# ProPrj__G__2025-07-30.net
KiCad netlist of a schematic drawn in EasyEDA Pro
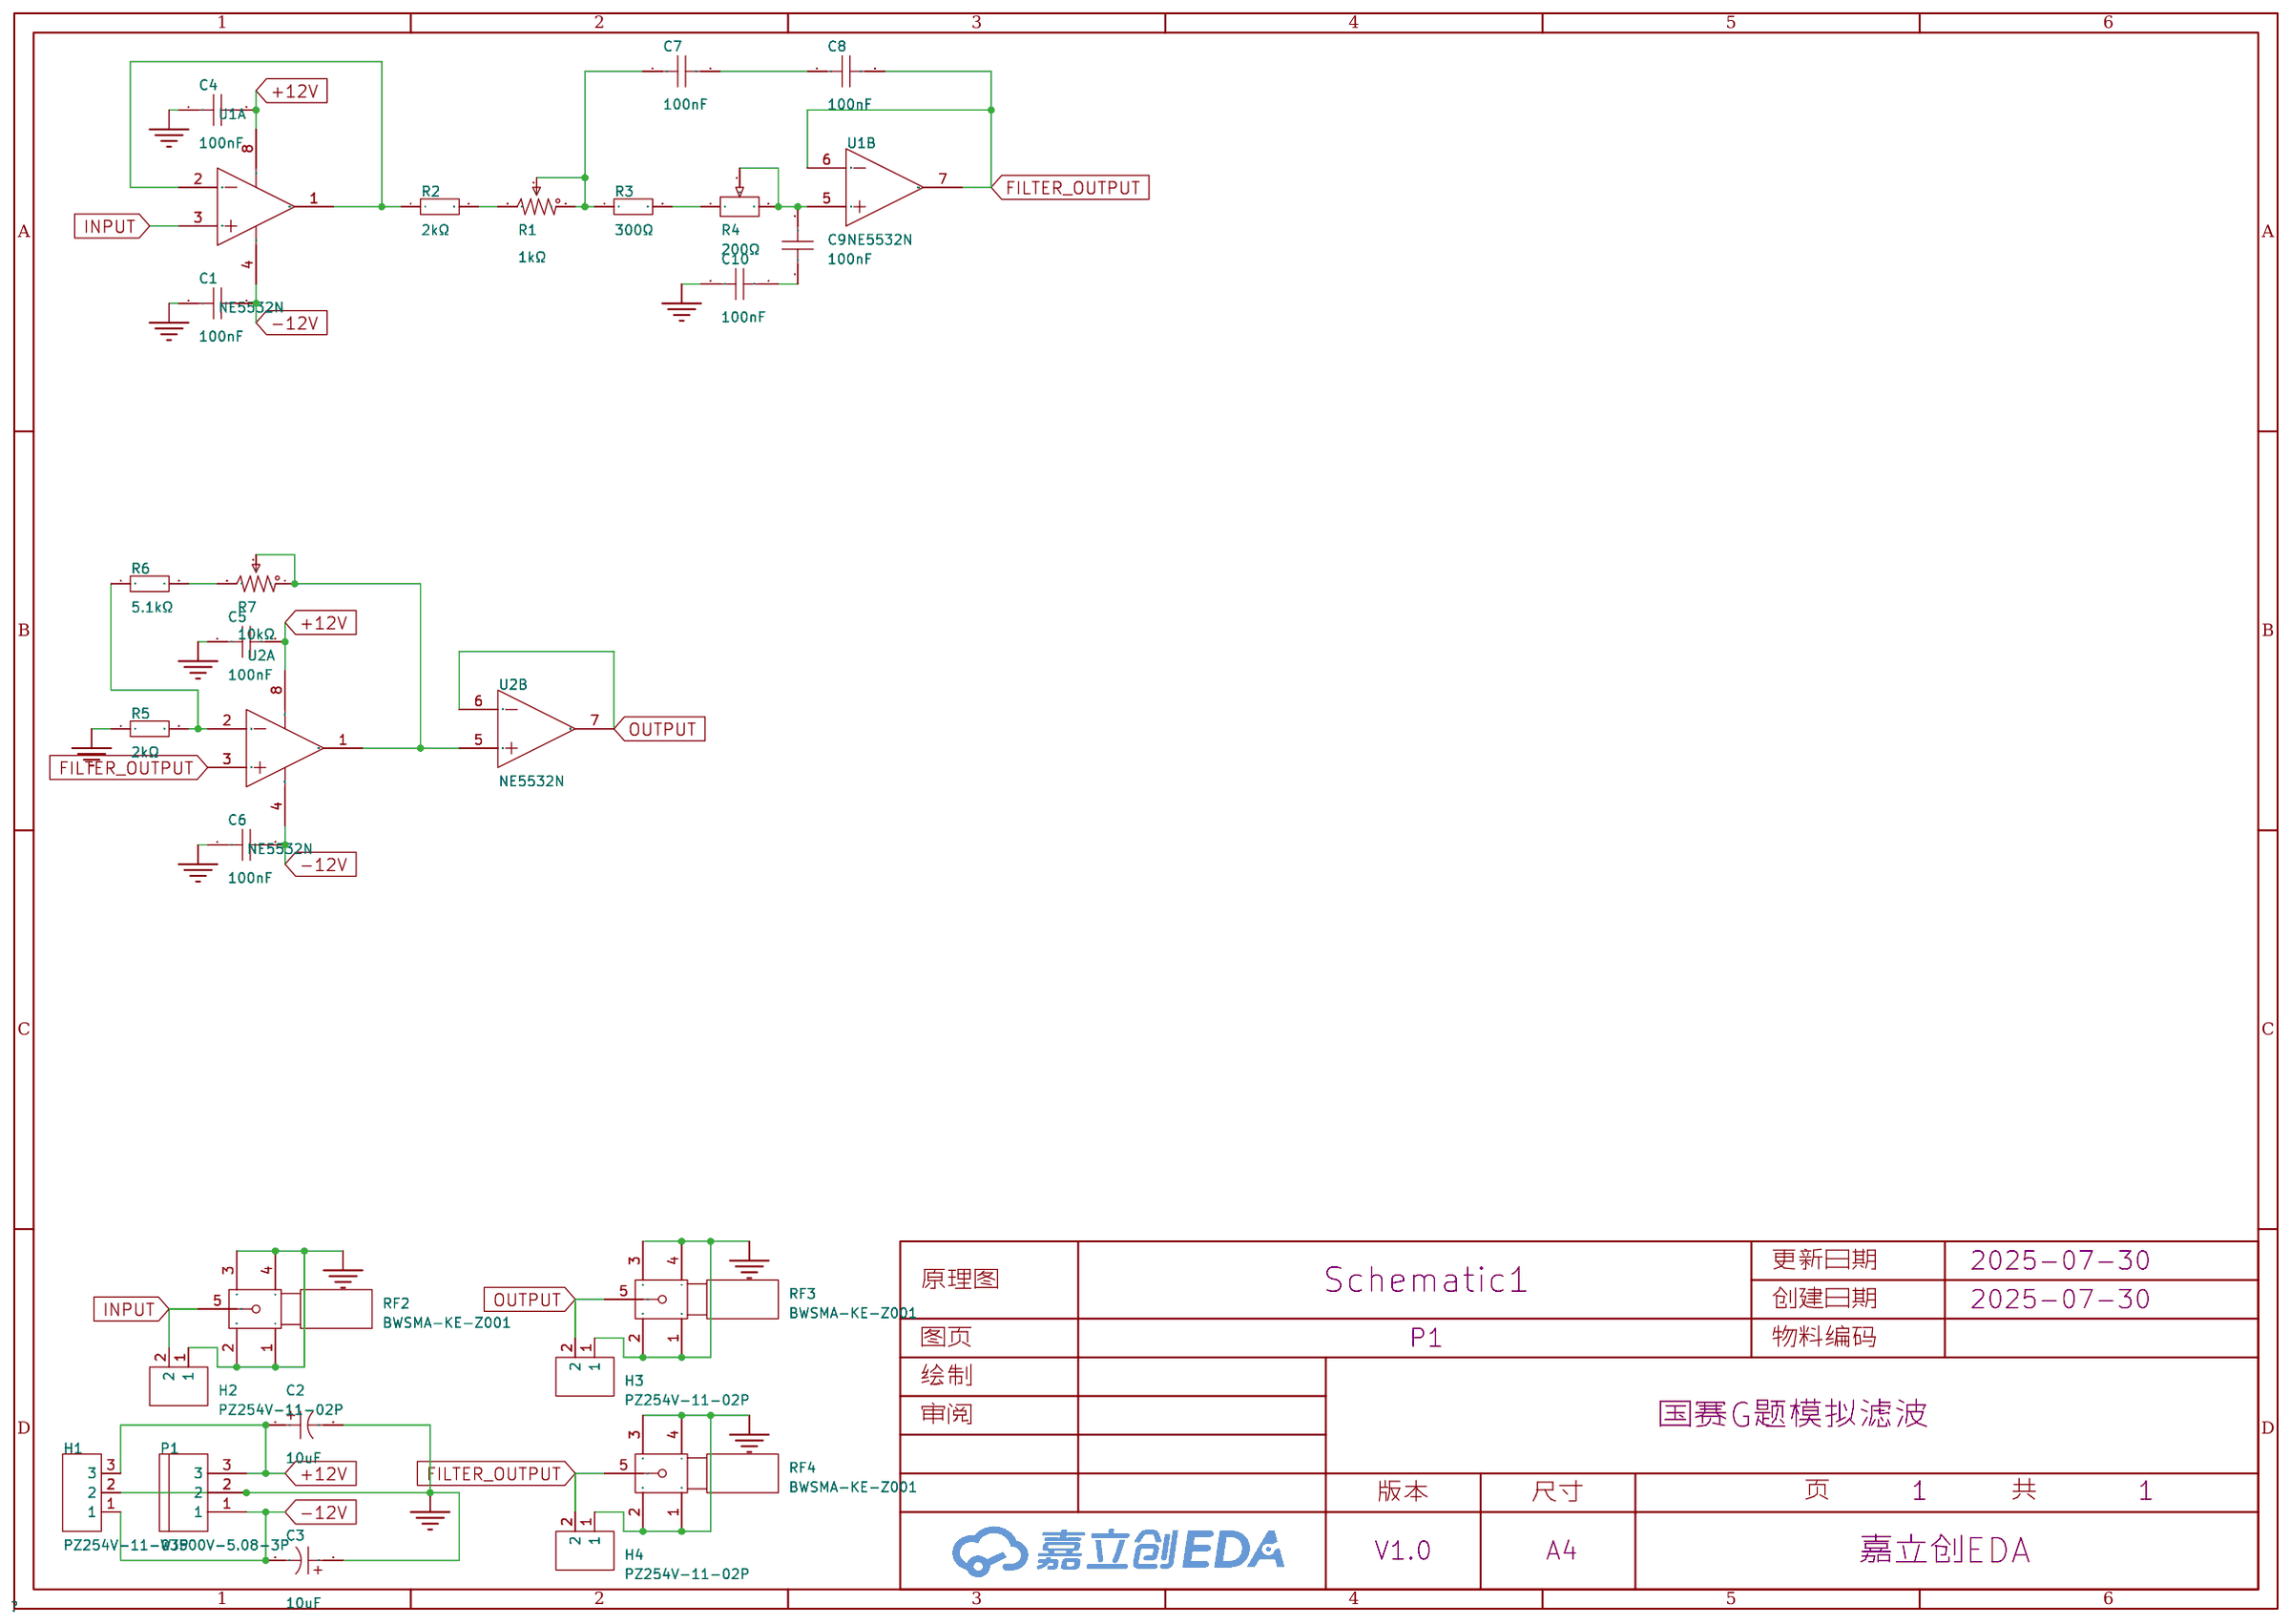
[diagram p0: schematic sheet]

(export (version "E")
  (design (tool "Eeschema 10.0.6"))
  (components
    (comp (ref "C1")
      (value "100nF")
      (footprint "easyedapro:CAP-TH_L5.8-W2.4-P2.54-D0.6")
      (description "容值:100nF;精度:-20%~+80%;额定电压:50V;温度系数:Y5V;")
      (fields
        (field (name "Manufacturer Part") "CC1H104ZA1ED3F5P1100")
        (field (name "Manufacturer") "Dersonic(德尔创)")
      )
      (libsource (lib "easyedapro") (part "CC1H104ZA1ED3F5P1100"))
    )
    (comp (ref "C2")
      (value "10uF")
      (footprint "easyedapro:CAP-TH_BD5.0-P2.00-D0.5-FD-A")
      (description "容值:10uF;精度:±20%;额定电压:25V;纹波电流:100mA@100kHz;等效串联电阻(ESR):3.3Ω@100kHz;")
      (fields (field (name "Manufacturer Part") "ERG450V10M10x16") (field (name "Manufacturer") "捷而瑞"))
      (libsource (lib "easyedapro") (part "ERG25V10M5X11"))
    )
    (comp (ref "C3")
      (value "10uF")
      (footprint "easyedapro:CAP-TH_BD5.0-P2.00-D0.5-FD-A")
      (description "容值:10uF;精度:±20%;额定电压:25V;纹波电流:100mA@100kHz;等效串联电阻(ESR):3.3Ω@100kHz;")
      (fields (field (name "Manufacturer Part") "ERG450V10M10x16") (field (name "Manufacturer") "捷而瑞"))
      (libsource (lib "easyedapro") (part "ERG25V10M5X11"))
    )
    (comp (ref "C4")
      (value "100nF")
      (footprint "easyedapro:CAP-TH_L5.8-W2.4-P2.54-D0.6")
      (description "容值:100nF;精度:-20%~+80%;额定电压:50V;温度系数:Y5V;")
      (fields
        (field (name "Manufacturer Part") "CC1H104ZA1ED3F5P1100")
        (field (name "Manufacturer") "Dersonic(德尔创)")
      )
      (libsource (lib "easyedapro") (part "CC1H104ZA1ED3F5P1100"))
    )
    (comp (ref "C5")
      (value "100nF")
      (footprint "easyedapro:CAP-TH_L5.8-W2.4-P2.54-D0.6")
      (description "容值:100nF;精度:-20%~+80%;额定电压:50V;温度系数:Y5V;")
      (fields
        (field (name "Manufacturer Part") "CC1H104ZA1ED3F5P1100")
        (field (name "Manufacturer") "Dersonic(德尔创)")
      )
      (libsource (lib "easyedapro") (part "CC1H104ZA1ED3F5P1100"))
    )
    (comp (ref "C6")
      (value "100nF")
      (footprint "easyedapro:CAP-TH_L5.8-W2.4-P2.54-D0.6")
      (description "容值:100nF;精度:-20%~+80%;额定电压:50V;温度系数:Y5V;")
      (fields
        (field (name "Manufacturer Part") "CC1H104ZA1ED3F5P1100")
        (field (name "Manufacturer") "Dersonic(德尔创)")
      )
      (libsource (lib "easyedapro") (part "CC1H104ZA1ED3F5P1100"))
    )
    (comp (ref "C7")
      (value "100nF")
      (footprint "easyedapro:CAP-TH_L5.8-W2.4-P2.54-D0.6")
      (description "容值:100nF;精度:-20%~+80%;额定电压:50V;温度系数:Y5V;")
      (fields
        (field (name "Manufacturer Part") "CC1H104ZA1ED3F5P1100")
        (field (name "Manufacturer") "Dersonic(德尔创)")
      )
      (libsource (lib "easyedapro") (part "CC1H104ZA1ED3F5P1100"))
    )
    (comp (ref "C8")
      (value "100nF")
      (footprint "easyedapro:CAP-TH_L5.8-W2.4-P2.54-D0.6")
      (description "容值:100nF;精度:-20%~+80%;额定电压:50V;温度系数:Y5V;")
      (fields
        (field (name "Manufacturer Part") "CC1H104ZA1ED3F5P1100")
        (field (name "Manufacturer") "Dersonic(德尔创)")
      )
      (libsource (lib "easyedapro") (part "CC1H104ZA1ED3F5P1100"))
    )
    (comp (ref "C9")
      (value "100nF")
      (footprint "easyedapro:CAP-TH_L5.8-W2.4-P2.54-D0.6")
      (description "容值:100nF;精度:-20%~+80%;额定电压:50V;温度系数:Y5V;")
      (fields
        (field (name "Manufacturer Part") "CC1H104ZA1ED3F5P1100")
        (field (name "Manufacturer") "Dersonic(德尔创)")
      )
      (libsource (lib "easyedapro") (part "CC1H104ZA1ED3F5P1100"))
    )
    (comp (ref "C10")
      (value "100nF")
      (footprint "easyedapro:CAP-TH_L5.8-W2.4-P2.54-D0.6")
      (description "容值:100nF;精度:-20%~+80%;额定电压:50V;温度系数:Y5V;")
      (fields
        (field (name "Manufacturer Part") "CC1H104ZA1ED3F5P1100")
        (field (name "Manufacturer") "Dersonic(德尔创)")
      )
      (libsource (lib "easyedapro") (part "CC1H104ZA1ED3F5P1100"))
    )
    (comp (ref "H1")
      (value "PZ254V-11-03P")
      (footprint "easyedapro:HDR-TH_3P-P2.54-V-M")
      (fields (field (name "Manufacturer") "XFCN(兴飞)"))
      (libsource (lib "easyedapro") (part "PZ254V-11-03P_C2937625"))
    )
    (comp (ref "H2")
      (value "PZ254V-11-02P")
      (footprint "easyedapro:HDR-TH_2P-P2.54-V-M")
      (fields (field (name "Manufacturer") "XFCN(兴飞)"))
      (libsource (lib "easyedapro") (part "PZ254V-11-02P"))
    )
    (comp (ref "H3")
      (value "PZ254V-11-02P")
      (footprint "easyedapro:HDR-TH_2P-P2.54-V-M")
      (fields (field (name "Manufacturer") "XFCN(兴飞)"))
      (libsource (lib "easyedapro") (part "PZ254V-11-02P"))
    )
    (comp (ref "H4")
      (value "PZ254V-11-02P")
      (footprint "easyedapro:HDR-TH_2P-P2.54-V-M")
      (fields (field (name "Manufacturer") "XFCN(兴飞)"))
      (libsource (lib "easyedapro") (part "PZ254V-11-02P"))
    )
    (comp (ref "P1")
      (value "WJ500V-5.08-3P")
      (footprint "easyedapro:CONN-TH_3P-P5.00_WJ500V-5.08-3P")
      (fields (field (name "Manufacturer") "KANGNEX(康奈克斯电气)"))
      (libsource (lib "easyedapro") (part "WJ500V-5.08-3P-14-00A"))
    )
    (comp (ref "R1")
      (value "1kΩ")
      (footprint "easyedapro:RES-ADJ-TH_3P-L10.0-W10.0-P2.50-BL-BS")
      (description "阻值:1kΩ;精度:±10%;")
      (fields (field (name "Manufacturer Part") "3296W-1-102") (field (name "Manufacturer") "BOCHEN(博晨)"))
      (libsource (lib "easyedapro") (part "3296W-1-102"))
    )
    (comp (ref "R2")
      (value "2kΩ")
      (footprint "easyedapro:Res_1/8W")
      (libsource (lib "easyedapro") (part "电阻"))
    )
    (comp (ref "R3")
      (value "300Ω")
      (footprint "easyedapro:Res_1/8W")
      (libsource (lib "easyedapro") (part "电阻"))
    )
    (comp (ref "R4")
      (value "200Ω")
      (footprint "easyedapro:RES-ADJ-TH_3P-L9.5-W4.9-P2.50-L_3296W")
      (description "阻值:200Ω;精度:±10%;")
      (fields (field (name "Manufacturer Part") "3296W-1-201") (field (name "Manufacturer") "BOCHEN(博晨)"))
      (libsource (lib "easyedapro") (part "3296W-1-201"))
    )
    (comp (ref "R5")
      (value "2kΩ")
      (footprint "easyedapro:Res_1/8W")
      (libsource (lib "easyedapro") (part "电阻"))
    )
    (comp (ref "R6")
      (value "5.1kΩ")
      (footprint "easyedapro:Res_1/8W")
      (libsource (lib "easyedapro") (part "电阻"))
    )
    (comp (ref "R7")
      (value "10kΩ")
      (footprint "easyedapro:RES-ADJ-TH_3P-L10.0-W10.0-P2.50-L")
      (description "阻值:10kΩ;精度:±10%;")
      (fields (field (name "Manufacturer Part") "3296W-1-103") (field (name "Manufacturer") "BOCHEN(博晨)"))
      (libsource (lib "easyedapro") (part "3296W-1-103"))
    )
    (comp (ref "RF2")
      (value "BWSMA-KE-Z001")
      (footprint "easyedapro:SMA-TH_BWSMA-KE-Z001")
      (fields (field (name "Manufacturer") "BAT WIRELESS(蝙蝠无线)"))
      (libsource (lib "easyedapro") (part "BWSMA-KE-Z001"))
    )
    (comp (ref "RF3")
      (value "BWSMA-KE-Z001")
      (footprint "easyedapro:SMA-TH_BWSMA-KE-Z001")
      (fields (field (name "Manufacturer") "BAT WIRELESS(蝙蝠无线)"))
      (libsource (lib "easyedapro") (part "BWSMA-KE-Z001"))
    )
    (comp (ref "RF4")
      (value "BWSMA-KE-Z001")
      (footprint "easyedapro:SMA-TH_BWSMA-KE-Z001")
      (fields (field (name "Manufacturer") "BAT WIRELESS(蝙蝠无线)"))
      (libsource (lib "easyedapro") (part "BWSMA-KE-Z001"))
    )
    (comp (ref "U1")
      (value "NE5532N")
      (footprint "easyedapro:DIP-8_L9.3-W6.4-P2.54-LS7.6-BL")
      (description "放大器数:双路;轨到轨:-;增益带宽积(GBP):10MHz;输入失调电压(Vos):5mV;压摆率(SR):11V/us;输入偏置电流(Ib):500nA;")
      (fields (field (name "Manufacturer") "HGSEMI(华冠)"))
      (libsource (lib "easyedapro") (part "NE5532N"))
    )
    (comp (ref "U2")
      (value "NE5532N")
      (footprint "easyedapro:DIP-8_L9.3-W6.4-P2.54-LS7.6-BL")
      (description "放大器数:双路;轨到轨:-;增益带宽积(GBP):10MHz;输入失调电压(Vos):5mV;压摆率(SR):11V/us;输入偏置电流(Ib):500nA;")
      (fields (field (name "Manufacturer") "HGSEMI(华冠)"))
      (libsource (lib "easyedapro") (part "NE5532N"))
    )
  )
  (nets
    (net (code "1") (name "+12V") (class "Default")
      (node (ref "C2") (pin "1") (pinfunction "1_1") (pintype "input"))
      (node (ref "C4") (pin "2") (pinfunction "2_2") (pintype "unspecified"))
      (node (ref "C5") (pin "2") (pinfunction "2_2") (pintype "unspecified"))
      (node (ref "H1") (pin "3") (pinfunction "3_3") (pintype "unspecified"))
      (node (ref "P1") (pin "3") (pinfunction "3_3") (pintype "unspecified"))
      (node (ref "U1") (pin "8") (pinfunction "VCC+_8") (pintype "unspecified"))
      (node (ref "U2") (pin "8") (pinfunction "VCC+_8") (pintype "unspecified"))
    )
    (net (code "2") (name "-12V") (class "Default")
      (node (ref "C1") (pin "2") (pinfunction "2_2") (pintype "unspecified"))
      (node (ref "C3") (pin "2") (pinfunction "2_2") (pintype "input"))
      (node (ref "C6") (pin "2") (pinfunction "2_2") (pintype "unspecified"))
      (node (ref "H1") (pin "1") (pinfunction "1_1") (pintype "unspecified"))
      (node (ref "P1") (pin "1") (pinfunction "1_1") (pintype "unspecified"))
      (node (ref "U1") (pin "4") (pinfunction "VCC-_4") (pintype "unspecified"))
      (node (ref "U2") (pin "4") (pinfunction "VCC-_4") (pintype "unspecified"))
    )
    (net (code "3") (name "FILTER_OUTPUT") (class "Default")
      (node (ref "C8") (pin "2") (pinfunction "2_2") (pintype "unspecified"))
      (node (ref "H4") (pin "2") (pinfunction "2_2") (pintype "unspecified"))
      (node (ref "RF4") (pin "5") (pinfunction "5_5") (pintype "unspecified"))
      (node (ref "U1") (pin "6") (pinfunction "IN2-_6") (pintype "unspecified"))
      (node (ref "U1") (pin "7") (pinfunction "OUT2_7") (pintype "output"))
      (node (ref "U2") (pin "3") (pinfunction "IN1+_3") (pintype "unspecified"))
    )
    (net (code "4") (name "GND") (class "Default")
      (node (ref "C1") (pin "1") (pinfunction "1_1") (pintype "unspecified"))
      (node (ref "C10") (pin "2") (pinfunction "2_2") (pintype "unspecified"))
      (node (ref "C2") (pin "2") (pinfunction "2_2") (pintype "input"))
      (node (ref "C3") (pin "1") (pinfunction "1_1") (pintype "input"))
      (node (ref "C4") (pin "1") (pinfunction "1_1") (pintype "unspecified"))
      (node (ref "C5") (pin "1") (pinfunction "1_1") (pintype "unspecified"))
      (node (ref "C6") (pin "1") (pinfunction "1_1") (pintype "unspecified"))
      (node (ref "H1") (pin "2") (pinfunction "2_2") (pintype "unspecified"))
      (node (ref "H2") (pin "1") (pinfunction "1_1") (pintype "unspecified"))
      (node (ref "H3") (pin "1") (pinfunction "1_1") (pintype "unspecified"))
      (node (ref "H4") (pin "1") (pinfunction "1_1") (pintype "unspecified"))
      (node (ref "P1") (pin "2") (pinfunction "2_2") (pintype "unspecified"))
      (node (ref "R5") (pin "1") (pinfunction "1_1") (pintype "input"))
      (node (ref "RF2") (pin "1") (pinfunction "1_1") (pintype "unspecified"))
      (node (ref "RF2") (pin "2") (pinfunction "2_2") (pintype "unspecified"))
      (node (ref "RF2") (pin "3") (pinfunction "3_3") (pintype "unspecified"))
      (node (ref "RF2") (pin "4") (pinfunction "4_4") (pintype "unspecified"))
      (node (ref "RF3") (pin "1") (pinfunction "1_1") (pintype "unspecified"))
      (node (ref "RF3") (pin "2") (pinfunction "2_2") (pintype "unspecified"))
      (node (ref "RF3") (pin "3") (pinfunction "3_3") (pintype "unspecified"))
      (node (ref "RF3") (pin "4") (pinfunction "4_4") (pintype "unspecified"))
      (node (ref "RF4") (pin "1") (pinfunction "1_1") (pintype "unspecified"))
      (node (ref "RF4") (pin "2") (pinfunction "2_2") (pintype "unspecified"))
      (node (ref "RF4") (pin "3") (pinfunction "3_3") (pintype "unspecified"))
      (node (ref "RF4") (pin "4") (pinfunction "4_4") (pintype "unspecified"))
    )
    (net (code "5") (name "INPUT") (class "Default")
      (node (ref "H2") (pin "2") (pinfunction "2_2") (pintype "unspecified"))
      (node (ref "RF2") (pin "5") (pinfunction "5_5") (pintype "unspecified"))
      (node (ref "U1") (pin "3") (pinfunction "IN1+_3") (pintype "unspecified"))
    )
    (net (code "6") (name "Net-(C7-Pad1)") (class "Default")
      (node (ref "C7") (pin "1") (pinfunction "1_1") (pintype "unspecified"))
      (node (ref "R1") (pin "1") (pinfunction "1_1") (pintype "unspecified"))
      (node (ref "R1") (pin "2") (pinfunction "2_2") (pintype "unspecified"))
      (node (ref "R3") (pin "1") (pinfunction "1_1") (pintype "input"))
    )
    (net (code "7") (name "Net-(C7-Pad2)") (class "Default")
      (node (ref "C7") (pin "2") (pinfunction "2_2") (pintype "unspecified"))
      (node (ref "C8") (pin "1") (pinfunction "1_1") (pintype "unspecified"))
    )
    (net (code "8") (name "Net-(C10-Pad1)") (class "Default")
      (node (ref "C10") (pin "1") (pinfunction "1_1") (pintype "unspecified"))
      (node (ref "C9") (pin "1") (pinfunction "1_1") (pintype "unspecified"))
    )
    (net (code "9") (name "Net-(R1-Pad3)") (class "Default")
      (node (ref "R1") (pin "3") (pinfunction "3_3") (pintype "unspecified"))
      (node (ref "R2") (pin "2") (pinfunction "2_2") (pintype "input"))
    )
    (net (code "10") (name "Net-(R3-Pad2)") (class "Default")
      (node (ref "R3") (pin "2") (pinfunction "2_2") (pintype "input"))
      (node (ref "R4") (pin "1") (pinfunction "1_1") (pintype "input"))
    )
    (net (code "11") (name "Net-(R6-Pad2)") (class "Default")
      (node (ref "R6") (pin "2") (pinfunction "2_2") (pintype "input"))
      (node (ref "R7") (pin "3") (pinfunction "3_3") (pintype "unspecified"))
    )
    (net (code "12") (name "Net-(U1A-IN1-)") (class "Default")
      (node (ref "R2") (pin "1") (pinfunction "1_1") (pintype "input"))
      (node (ref "U1") (pin "1") (pinfunction "OUT1_1") (pintype "output"))
      (node (ref "U1") (pin "2") (pinfunction "IN1-_2") (pintype "unspecified"))
    )
    (net (code "13") (name "Net-(U1B-IN2+)") (class "Default")
      (node (ref "C9") (pin "2") (pinfunction "2_2") (pintype "unspecified"))
      (node (ref "R4") (pin "2") (pinfunction "2_2") (pintype "input"))
      (node (ref "R4") (pin "3") (pinfunction "3_3") (pintype "input"))
      (node (ref "U1") (pin "5") (pinfunction "IN2+_5") (pintype "unspecified"))
    )
    (net (code "14") (name "Net-(U2A-IN1-)") (class "Default")
      (node (ref "R5") (pin "2") (pinfunction "2_2") (pintype "input"))
      (node (ref "R6") (pin "1") (pinfunction "1_1") (pintype "input"))
      (node (ref "U2") (pin "2") (pinfunction "IN1-_2") (pintype "unspecified"))
    )
    (net (code "15") (name "Net-(U2A-OUT1)") (class "Default")
      (node (ref "R7") (pin "1") (pinfunction "1_1") (pintype "unspecified"))
      (node (ref "R7") (pin "2") (pinfunction "2_2") (pintype "unspecified"))
      (node (ref "U2") (pin "1") (pinfunction "OUT1_1") (pintype "output"))
      (node (ref "U2") (pin "5") (pinfunction "IN2+_5") (pintype "unspecified"))
    )
    (net (code "16") (name "OUTPUT") (class "Default")
      (node (ref "H3") (pin "2") (pinfunction "2_2") (pintype "unspecified"))
      (node (ref "RF3") (pin "5") (pinfunction "5_5") (pintype "unspecified"))
      (node (ref "U2") (pin "6") (pinfunction "IN2-_6") (pintype "unspecified"))
      (node (ref "U2") (pin "7") (pinfunction "OUT2_7") (pintype "output"))
    )
  )
)
